# PHONE.net
KiCad netlist of a schematic drawn in Altium Designer
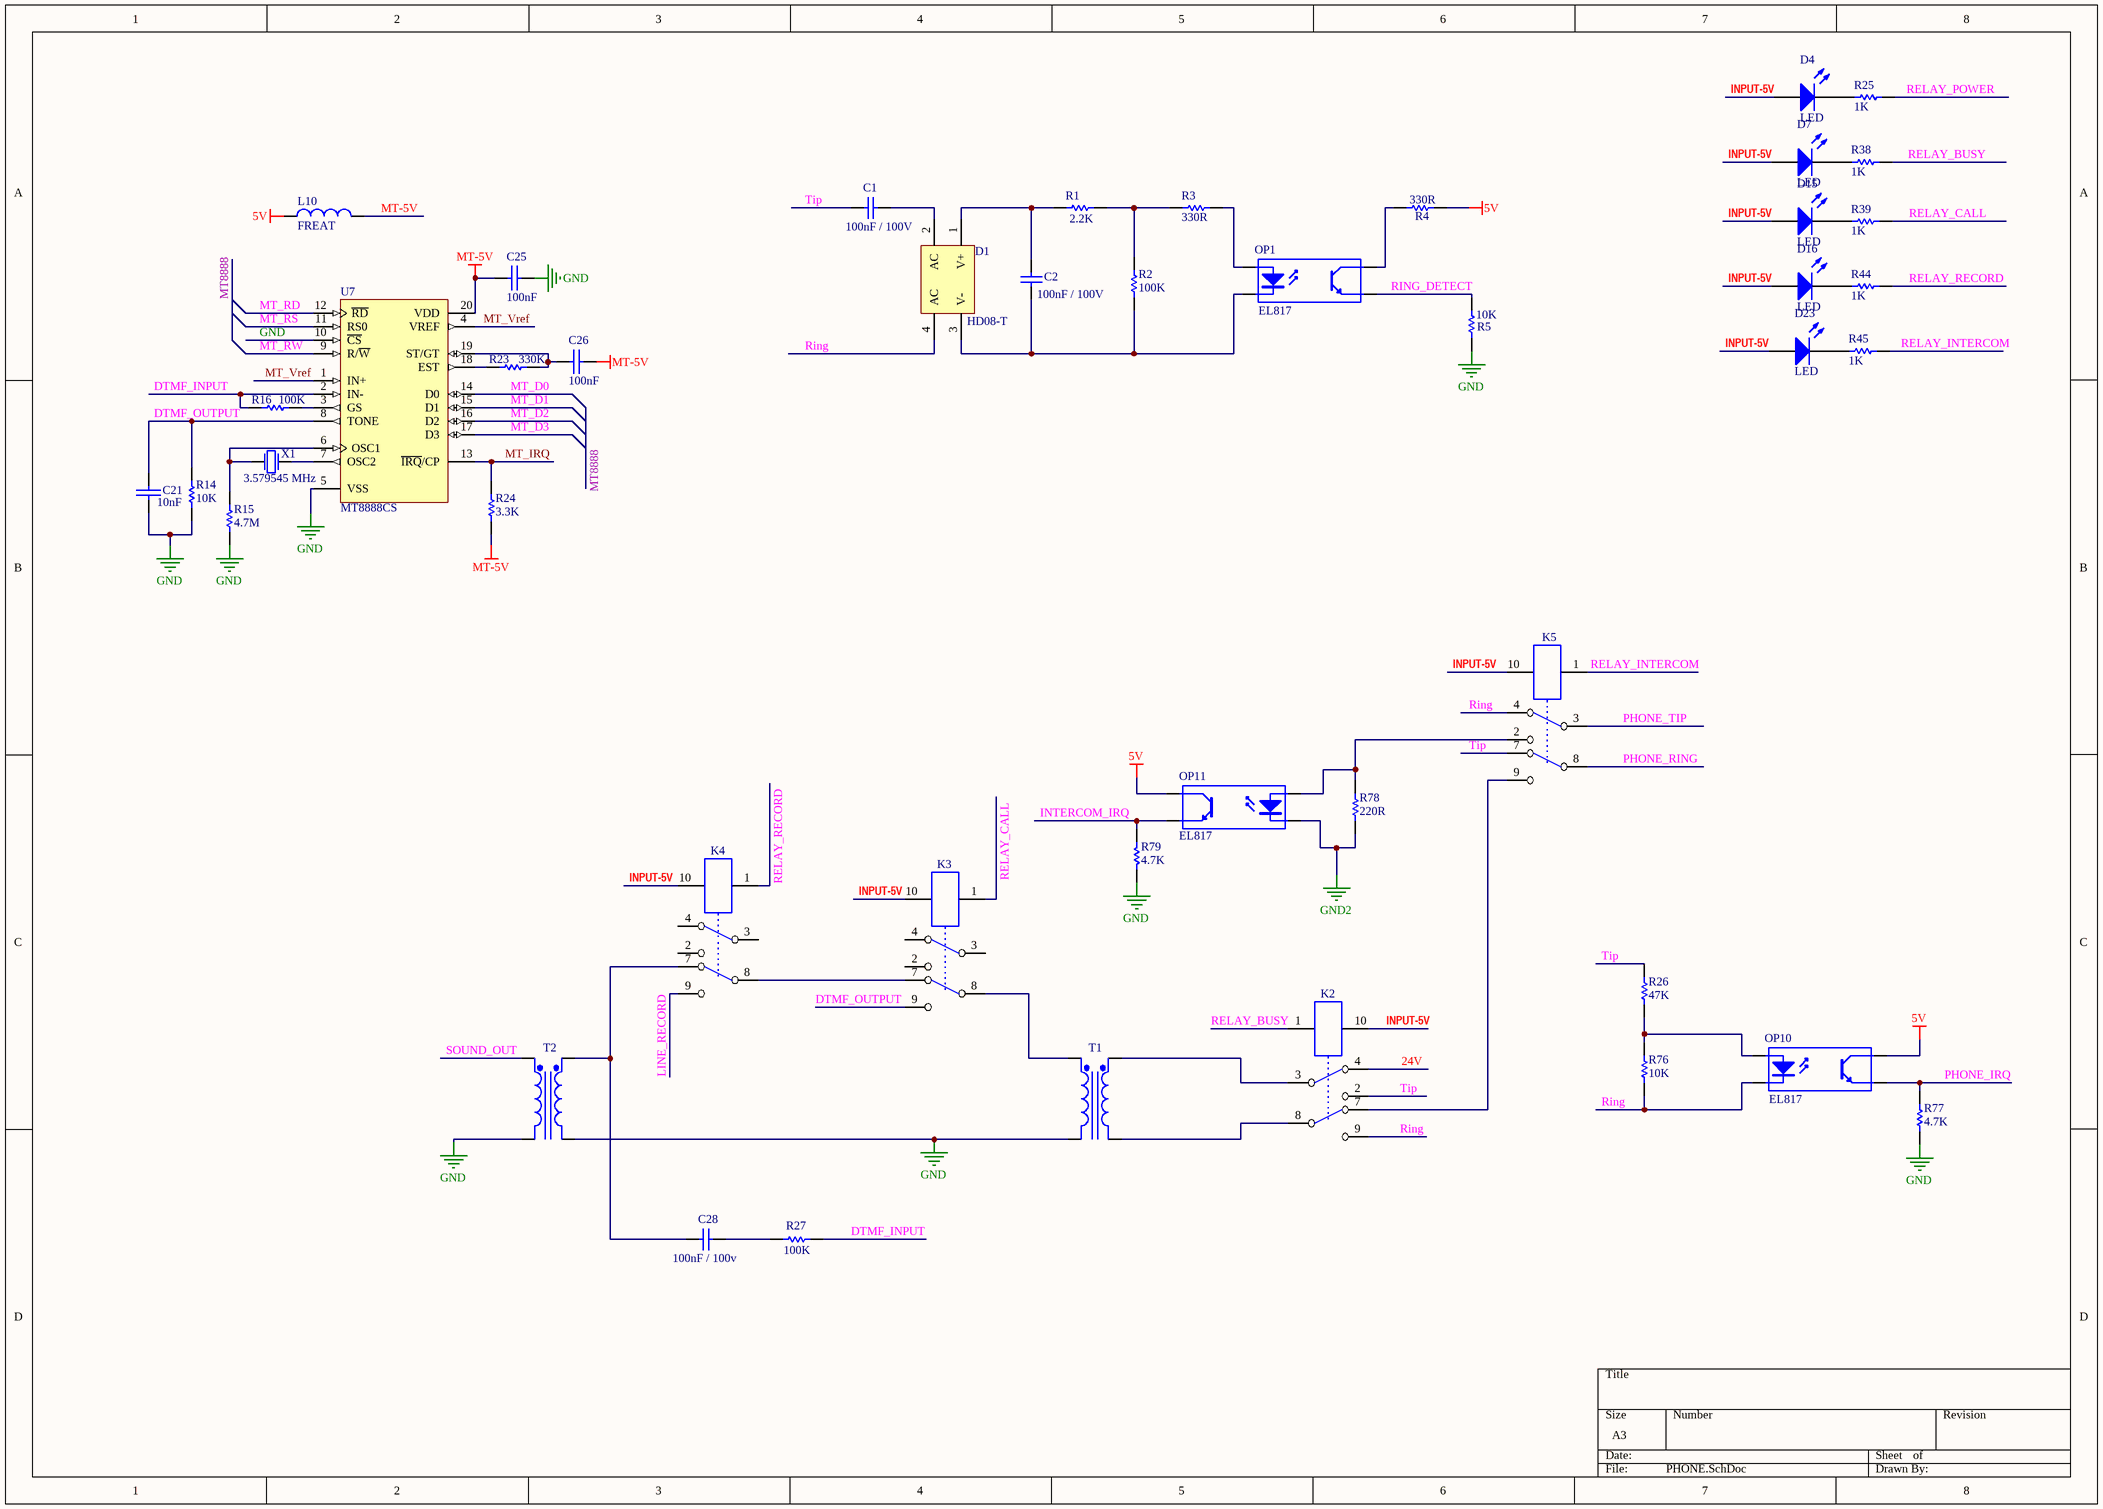
[diagram p0: PHONE.SchDoc]

(export (version "E")
  (design (tool "Eeschema 10.0.6"))
  (components
    (comp (ref "C1")
      (value "100nF / 100V")
      (footprint "RAD-0.3")
      (description "Capacitor")
      (fields (field (name "PUBLISHER") "Altium Limited"))
      (libsource (lib "Miscellaneous Devices") (part "Cap"))
    )
    (comp (ref "C2")
      (value "100nF / 100V")
      (footprint "RAD-0.3")
      (description "Capacitor")
      (fields (field (name "PUBLISHER") "Altium Limited"))
      (libsource (lib "Miscellaneous Devices") (part "Cap"))
    )
    (comp (ref "C21") (value "10nF") (footprint "0805c") (libsource (lib "*") (part "CAP")))
    (comp (ref "C25") (value "100nF") (footprint "0805c") (libsource (lib "*") (part "CAP")))
    (comp (ref "C26") (value "100nF") (footprint "0805c") (libsource (lib "*") (part "CAP")))
    (comp (ref "C28")
      (value "100nF / 100v")
      (footprint "1206")
      (description "Capacitor")
      (fields (field (name "Comment") "100uF / 100V") (field (name "PUBLISHER") "Altium Limited"))
      (libsource (lib "Miscellaneous Devices") (part "Cap"))
    )
    (comp (ref "D1")
      (value "HD08-T")
      (footprint "HD08-T")
      (description "Diode Bridge")
      (fields (field (name "PUBLISHER") "Altium Limited"))
      (libsource (lib "Miscellaneous Devices") (part "Bridge2"))
    )
    (comp (ref "D4")
      (value "LED")
      (footprint "0805d")
      (description "Typical RED GaAs LED")
      (fields (field (name "PUBLISHER") "Altium Limited"))
      (libsource (lib "Miscellaneous Devices") (part "LED1"))
    )
    (comp (ref "D7")
      (value "LED")
      (footprint "0805d")
      (description "Typical RED GaAs LED")
      (fields (field (name "PUBLISHER") "Altium Limited"))
      (libsource (lib "Miscellaneous Devices") (part "LED1"))
    )
    (comp (ref "D15")
      (value "LED")
      (footprint "0805d")
      (description "Typical RED GaAs LED")
      (fields (field (name "PUBLISHER") "Altium Limited"))
      (libsource (lib "Miscellaneous Devices") (part "LED1"))
    )
    (comp (ref "D16")
      (value "LED")
      (footprint "0805d")
      (description "Typical RED GaAs LED")
      (fields (field (name "PUBLISHER") "Altium Limited"))
      (libsource (lib "Miscellaneous Devices") (part "LED1"))
    )
    (comp (ref "D23")
      (value "LED")
      (footprint "0805d")
      (description "Typical RED GaAs LED")
      (fields (field (name "PUBLISHER") "Altium Limited"))
      (libsource (lib "Miscellaneous Devices") (part "LED1"))
    )
    (comp (ref "K2")
      (value "RELAY 5V")
      (footprint "RELAY G6H")
      (libsource (lib "*") (part "RELAY DPDT-G6HU"))
    )
    (comp (ref "K3")
      (value "RELAY 5V")
      (footprint "RELAY G6H")
      (libsource (lib "*") (part "RELAY DPDT-G6HU"))
    )
    (comp (ref "K4")
      (value "RELAY 5V")
      (footprint "RELAY G6H")
      (libsource (lib "*") (part "RELAY DPDT-G6HU"))
    )
    (comp (ref "K5")
      (value "RELAY 5V")
      (footprint "RELAY G6H")
      (libsource (lib "*") (part "RELAY DPDT-G6HU"))
    )
    (comp (ref "L10")
      (value "FREAT")
      (footprint "1206")
      (description "Inductor")
      (fields (field (name "PUBLISHER") "Altium Limited"))
      (libsource (lib "Miscellaneous Devices") (part "Inductor"))
    )
    (comp (ref "OP1")
      (value "EL817")
      (footprint "EL817")
      (description "4-Pin Phototransistor Optocoupler")
      (fields (field (name "PUBLISHER") "Altium Limited"))
      (libsource (lib "Miscellaneous Devices") (part "Optoisolator1"))
    )
    (comp (ref "OP10")
      (value "EL817")
      (footprint "EL817")
      (description "4-Pin Phototransistor Optocoupler")
      (fields (field (name "PUBLISHER") "Altium Limited"))
      (libsource (lib "Miscellaneous Devices") (part "Optoisolator1"))
    )
    (comp (ref "OP11")
      (value "EL817")
      (footprint "EL817")
      (description "4-Pin Phototransistor Optocoupler")
      (fields (field (name "PUBLISHER") "Altium Limited"))
      (libsource (lib "Miscellaneous Devices") (part "Optoisolator1"))
    )
    (comp (ref "R1")
      (value "2.2K")
      (footprint "0805")
      (description "Semiconductor Resistor")
      (fields (field (name "PUBLISHER") "Altium Limited"))
      (libsource (lib "Miscellaneous Devices") (part "Res Semi"))
    )
    (comp (ref "R2")
      (value "100K")
      (footprint "0805")
      (description "Semiconductor Resistor")
      (fields (field (name "PUBLISHER") "Altium Limited"))
      (libsource (lib "Miscellaneous Devices") (part "Res Semi"))
    )
    (comp (ref "R3")
      (value "330R")
      (footprint "0805")
      (description "Semiconductor Resistor")
      (fields (field (name "PUBLISHER") "Altium Limited"))
      (libsource (lib "Miscellaneous Devices") (part "Res Semi"))
    )
    (comp (ref "R4")
      (value "330R")
      (footprint "0805")
      (description "Semiconductor Resistor")
      (fields (field (name "PUBLISHER") "Altium Limited"))
      (libsource (lib "Miscellaneous Devices") (part "Res Semi"))
    )
    (comp (ref "R5")
      (value "10K")
      (footprint "0805")
      (description "Semiconductor Resistor")
      (fields (field (name "PUBLISHER") "Altium Limited"))
      (libsource (lib "Miscellaneous Devices") (part "Res Semi"))
    )
    (comp (ref "R14")
      (value "10K")
      (footprint "0805")
      (description "Semiconductor Resistor")
      (fields (field (name "PUBLISHER") "Altium Limited"))
      (libsource (lib "Miscellaneous Devices") (part "Res Semi"))
    )
    (comp (ref "R15")
      (value "4.7M")
      (footprint "0805")
      (description "Semiconductor Resistor")
      (fields (field (name "PUBLISHER") "Altium Limited"))
      (libsource (lib "Miscellaneous Devices") (part "Res Semi"))
    )
    (comp (ref "R16")
      (value "100K")
      (footprint "0805")
      (description "Semiconductor Resistor")
      (fields (field (name "PUBLISHER") "Altium Limited"))
      (libsource (lib "Miscellaneous Devices") (part "Res Semi"))
    )
    (comp (ref "R23")
      (value "330K")
      (footprint "0805")
      (description "Semiconductor Resistor")
      (fields (field (name "Comment") "374K") (field (name "PUBLISHER") "Altium Limited"))
      (libsource (lib "Miscellaneous Devices") (part "Res Semi"))
    )
    (comp (ref "R24")
      (value "3.3K")
      (footprint "0805")
      (description "Semiconductor Resistor")
      (fields (field (name "PUBLISHER") "Altium Limited"))
      (libsource (lib "Miscellaneous Devices") (part "Res Semi"))
    )
    (comp (ref "R25")
      (value "1K")
      (footprint "0805")
      (description "Resistor")
      (fields (field (name "PUBLISHER") "Altium Limited"))
      (libsource (lib "Miscellaneous Devices") (part "Res1"))
    )
    (comp (ref "R26")
      (value "47K")
      (footprint "0805")
      (description "Semiconductor Resistor")
      (fields (field (name "PUBLISHER") "Altium Limited"))
      (libsource (lib "Miscellaneous Devices") (part "Res Semi"))
    )
    (comp (ref "R27")
      (value "100K")
      (footprint "0805")
      (description "Semiconductor Resistor")
      (fields (field (name "PUBLISHER") "Altium Limited"))
      (libsource (lib "Miscellaneous Devices") (part "Res Semi"))
    )
    (comp (ref "R38")
      (value "1K")
      (footprint "0805")
      (description "Resistor")
      (fields (field (name "PUBLISHER") "Altium Limited"))
      (libsource (lib "Miscellaneous Devices") (part "Res1"))
    )
    (comp (ref "R39")
      (value "1K")
      (footprint "0805")
      (description "Resistor")
      (fields (field (name "PUBLISHER") "Altium Limited"))
      (libsource (lib "Miscellaneous Devices") (part "Res1"))
    )
    (comp (ref "R44")
      (value "1K")
      (footprint "0805")
      (description "Resistor")
      (fields (field (name "PUBLISHER") "Altium Limited"))
      (libsource (lib "Miscellaneous Devices") (part "Res1"))
    )
    (comp (ref "R45")
      (value "1K")
      (footprint "0805")
      (description "Resistor")
      (fields (field (name "PUBLISHER") "Altium Limited"))
      (libsource (lib "Miscellaneous Devices") (part "Res1"))
    )
    (comp (ref "R76")
      (value "10K")
      (footprint "0805")
      (description "Semiconductor Resistor")
      (fields (field (name "PUBLISHER") "Altium Limited"))
      (libsource (lib "Miscellaneous Devices") (part "Res Semi"))
    )
    (comp (ref "R77")
      (value "4.7K")
      (footprint "0805")
      (description "Semiconductor Resistor")
      (fields (field (name "PUBLISHER") "Altium Limited"))
      (libsource (lib "Miscellaneous Devices") (part "Res Semi"))
    )
    (comp (ref "R78")
      (value "220R")
      (footprint "0805")
      (description "Semiconductor Resistor")
      (fields (field (name "Comment") "220") (field (name "PUBLISHER") "Altium Limited"))
      (libsource (lib "Miscellaneous Devices") (part "Res Semi"))
    )
    (comp (ref "R79")
      (value "4.7K")
      (footprint "0805")
      (description "Semiconductor Resistor")
      (fields (field (name "PUBLISHER") "Altium Limited"))
      (libsource (lib "Miscellaneous Devices") (part "Res Semi"))
    )
    (comp (ref "T1")
      (value "TRANCE 300 :300")
      (footprint "trance")
      (description "Transformer (Ideal)")
      (fields (field (name "PUBLISHER") "Altium Limited"))
      (libsource (lib "Miscellaneous Devices") (part "Trans Ideal"))
    )
    (comp (ref "T2")
      (value "TRANCE 300 :300")
      (footprint "trance")
      (description "Transformer (Ideal)")
      (fields (field (name "PUBLISHER") "Altium Limited"))
      (libsource (lib "Miscellaneous Devices") (part "Trans Ideal"))
    )
    (comp (ref "U7")
      (value "MT8888CS")
      (footprint "SOIC20_N")
      (description "Integrated DTMF Transceiver with Intel Micro Interface")
      (fields (field (name "PUBLISHER") "Altium Limited"))
      (libsource (lib "Zarlink Comm DTMF Receiver") (part "MT8888CS"))
    )
    (comp (ref "X1")
      (value "3.579545 MHz")
      (footprint "crystal")
      (description "Crystal Oscillator")
      (libsource (lib "*") (part "16.000MHZ"))
    )
  )
  (nets
    (net (code "2") (name "/24V") (class "Default")
      (node (ref "K2") (pin "4") (pinfunction "NC1_4") (pintype "passive"))
    )
    (net (code "3") (name "/DTMF_INPUT") (class "Default")
      (node (ref "R16") (pin "2") (pinfunction "2_2") (pintype "passive"))
      (node (ref "R27") (pin "1") (pinfunction "1_1") (pintype "passive"))
      (node (ref "U7") (pin "2") (pinfunction "IN-_2") (pintype "input"))
    )
    (net (code "4") (name "/DTMF_OUTPUT") (class "Default")
      (node (ref "C21") (pin "1") (pintype "passive"))
      (node (ref "K3") (pin "9") (pinfunction "NO2_9") (pintype "passive"))
      (node (ref "R14") (pin "2") (pinfunction "2_2") (pintype "passive"))
      (node (ref "U7") (pin "8") (pinfunction "TONE_8") (pintype "output"))
    )
    (net (code "5") (name "/INPUT-5V") (class "Default")
      (node (ref "D15") (pin "1") (pinfunction "A_1") (pintype "passive"))
      (node (ref "D16") (pin "1") (pinfunction "A_1") (pintype "passive"))
      (node (ref "D23") (pin "1") (pinfunction "A_1") (pintype "passive"))
      (node (ref "D4") (pin "1") (pinfunction "A_1") (pintype "passive"))
      (node (ref "D7") (pin "1") (pinfunction "A_1") (pintype "passive"))
      (node (ref "K2") (pin "10") (pinfunction "-_10") (pintype "passive"))
      (node (ref "K3") (pin "10") (pinfunction "-_10") (pintype "passive"))
      (node (ref "K4") (pin "10") (pinfunction "-_10") (pintype "passive"))
      (node (ref "K5") (pin "10") (pinfunction "-_10") (pintype "passive"))
    )
    (net (code "6") (name "/INTERCOM_IRQ") (class "Default")
      (node (ref "OP11") (pin "3") (pinfunction "E_3") (pintype "passive"))
      (node (ref "R79") (pin "1") (pinfunction "1_1") (pintype "passive"))
    )
    (net (code "7") (name "/LINE_RECORD") (class "Default")
      (node (ref "K4") (pin "9") (pinfunction "NO2_9") (pintype "passive"))
    )
    (net (code "8") (name "/MT_D0") (class "Default")
      (node (ref "U7") (pin "14") (pinfunction "D0_14") (pintype "bidirectional"))
    )
    (net (code "9") (name "/MT_D1") (class "Default")
      (node (ref "U7") (pin "15") (pinfunction "D1_15") (pintype "bidirectional"))
    )
    (net (code "10") (name "/MT_D2") (class "Default")
      (node (ref "U7") (pin "16") (pinfunction "D2_16") (pintype "bidirectional"))
    )
    (net (code "11") (name "/MT_D3") (class "Default")
      (node (ref "U7") (pin "17") (pinfunction "D3_17") (pintype "bidirectional"))
    )
    (net (code "12") (name "/MT_IRQ") (class "Default")
      (node (ref "R24") (pin "2") (pinfunction "2_2") (pintype "passive"))
      (node (ref "U7") (pin "13") (pinfunction "~{IRQ}/CP_13") (pintype "open_collector"))
    )
    (net (code "13") (name "/MT_RD") (class "Default")
      (node (ref "U7") (pin "12") (pinfunction "~{RD}_12") (pintype "input"))
    )
    (net (code "14") (name "/MT_RS") (class "Default")
      (node (ref "U7") (pin "11") (pinfunction "RS0_11") (pintype "input"))
    )
    (net (code "15") (name "/MT_RW") (class "Default")
      (node (ref "U7") (pin "9") (pinfunction "R/~{W}_9") (pintype "input"))
    )
    (net (code "16") (name "/MT_Vref") (class "Default")
      (node (ref "U7") (pin "1") (pinfunction "IN+_1") (pintype "input"))
      (node (ref "U7") (pin "4") (pinfunction "VREF_4") (pintype "output"))
    )
    (net (code "17") (name "/PHONE_IRQ") (class "Default")
      (node (ref "OP10") (pin "3") (pinfunction "E_3") (pintype "passive"))
      (node (ref "R77") (pin "1") (pinfunction "1_1") (pintype "passive"))
    )
    (net (code "18") (name "/PHONE_RING") (class "Default")
      (node (ref "K5") (pin "8") (pinfunction "C2_8") (pintype "passive"))
    )
    (net (code "19") (name "/PHONE_TIP") (class "Default")
      (node (ref "K5") (pin "3") (pinfunction "C1_3") (pintype "passive"))
    )
    (net (code "20") (name "/RELAY_BUSY") (class "Default")
      (node (ref "K2") (pin "1") (pinfunction "+_1") (pintype "passive"))
      (node (ref "R38") (pin "2") (pinfunction "2_2") (pintype "passive"))
    )
    (net (code "21") (name "/RELAY_CALL") (class "Default")
      (node (ref "K3") (pin "1") (pinfunction "+_1") (pintype "passive"))
      (node (ref "R39") (pin "2") (pinfunction "2_2") (pintype "passive"))
    )
    (net (code "22") (name "/RELAY_INTERCOM") (class "Default")
      (node (ref "K5") (pin "1") (pinfunction "+_1") (pintype "passive"))
      (node (ref "R45") (pin "2") (pinfunction "2_2") (pintype "passive"))
    )
    (net (code "23") (name "/RELAY_POWER") (class "Default")
      (node (ref "R25") (pin "2") (pinfunction "2_2") (pintype "passive"))
    )
    (net (code "24") (name "/RELAY_RECORD") (class "Default")
      (node (ref "K4") (pin "1") (pinfunction "+_1") (pintype "passive"))
      (node (ref "R44") (pin "2") (pinfunction "2_2") (pintype "passive"))
    )
    (net (code "25") (name "/RING_DETECT") (class "Default")
      (node (ref "OP1") (pin "3") (pinfunction "E_3") (pintype "passive"))
      (node (ref "R5") (pin "2") (pinfunction "2_2") (pintype "passive"))
    )
    (net (code "26") (name "/Ring") (class "Default")
      (node (ref "D1") (pin "4") (pinfunction "AC_4") (pintype "passive"))
      (node (ref "K2") (pin "9") (pinfunction "NO2_9") (pintype "passive"))
      (node (ref "K5") (pin "4") (pinfunction "NC1_4") (pintype "passive"))
      (node (ref "OP10") (pin "2") (pinfunction "K_2") (pintype "passive"))
      (node (ref "R76") (pin "2") (pinfunction "2_2") (pintype "passive"))
    )
    (net (code "27") (name "/SOUND_OUT") (class "Default")
      (node (ref "T2") (pin "1") (pinfunction "Pri+_1") (pintype "passive"))
    )
    (net (code "28") (name "/Tip") (class "Default")
      (node (ref "C1") (pin "2") (pinfunction "2_2") (pintype "passive"))
      (node (ref "K2") (pin "2") (pinfunction "NO1_2") (pintype "passive"))
      (node (ref "K5") (pin "7") (pinfunction "NC2_7") (pintype "passive"))
      (node (ref "R26") (pin "2") (pinfunction "2_2") (pintype "passive"))
    )
    (net (code "30") (name "5V") (class "Default")
      (node (ref "L10") (pin "2") (pinfunction "2_2") (pintype "passive"))
      (node (ref "OP10") (pin "4") (pinfunction "C_4") (pintype "passive"))
      (node (ref "OP11") (pin "4") (pinfunction "C_4") (pintype "passive"))
      (node (ref "R4") (pin "2") (pinfunction "2_2") (pintype "passive"))
    )
    (net (code "31") (name "GND") (class "Default")
      (node (ref "C21") (pin "2") (pintype "passive"))
      (node (ref "C25") (pin "1") (pintype "passive"))
      (node (ref "R14") (pin "1") (pinfunction "1_1") (pintype "passive"))
      (node (ref "R15") (pin "1") (pinfunction "1_1") (pintype "passive"))
      (node (ref "R5") (pin "1") (pinfunction "1_1") (pintype "passive"))
      (node (ref "R77") (pin "2") (pinfunction "2_2") (pintype "passive"))
      (node (ref "R79") (pin "2") (pinfunction "2_2") (pintype "passive"))
      (node (ref "T1") (pin "2") (pinfunction "Pri-_2") (pintype "passive"))
      (node (ref "T2") (pin "2") (pinfunction "Pri-_2") (pintype "passive"))
      (node (ref "T2") (pin "4") (pinfunction "Sec-_4") (pintype "passive"))
      (node (ref "U7") (pin "10") (pinfunction "~{CS}_10") (pintype "input"))
      (node (ref "U7") (pin "5") (pinfunction "VSS_5") (pintype "power_in"))
    )
    (net (code "32") (name "GND2") (class "Default")
      (node (ref "OP11") (pin "2") (pinfunction "K_2") (pintype "passive"))
      (node (ref "R78") (pin "2") (pinfunction "2_2") (pintype "passive"))
    )
    (net (code "33") (name "MT-5V") (class "Default")
      (node (ref "C25") (pin "2") (pintype "passive"))
      (node (ref "C26") (pin "1") (pintype "passive"))
      (node (ref "L10") (pin "1") (pinfunction "1_1") (pintype "passive"))
      (node (ref "R24") (pin "1") (pinfunction "1_1") (pintype "passive"))
      (node (ref "U7") (pin "20") (pinfunction "VDD_20") (pintype "power_in"))
    )
    (net (code "34") (name "Net-(C1-Pad1)") (class "Default")
      (node (ref "C1") (pin "1") (pinfunction "1_1") (pintype "passive"))
      (node (ref "D1") (pin "2") (pinfunction "AC_2") (pintype "passive"))
    )
    (net (code "35") (name "Net-(C28-Pad2)") (class "Default")
      (node (ref "C28") (pin "2") (pinfunction "2_2") (pintype "passive"))
      (node (ref "R27") (pin "2") (pinfunction "2_2") (pintype "passive"))
    )
    (net (code "36") (name "Net-(D1-V+)") (class "Default")
      (node (ref "C2") (pin "2") (pinfunction "2_2") (pintype "passive"))
      (node (ref "D1") (pin "1") (pinfunction "V+_1") (pintype "passive"))
      (node (ref "R1") (pin "1") (pinfunction "1_1") (pintype "passive"))
    )
    (net (code "37") (name "Net-(D1-V-)") (class "Default")
      (node (ref "C2") (pin "1") (pinfunction "1_1") (pintype "passive"))
      (node (ref "D1") (pin "3") (pinfunction "V-_3") (pintype "passive"))
      (node (ref "OP1") (pin "2") (pinfunction "K_2") (pintype "passive"))
      (node (ref "R2") (pin "2") (pinfunction "2_2") (pintype "passive"))
    )
    (net (code "38") (name "Net-(D4-K)") (class "Default")
      (node (ref "D4") (pin "2") (pinfunction "K_2") (pintype "passive"))
      (node (ref "R25") (pin "1") (pinfunction "1_1") (pintype "passive"))
    )
    (net (code "39") (name "Net-(D7-K)") (class "Default")
      (node (ref "D7") (pin "2") (pinfunction "K_2") (pintype "passive"))
      (node (ref "R38") (pin "1") (pinfunction "1_1") (pintype "passive"))
    )
    (net (code "40") (name "Net-(D15-K)") (class "Default")
      (node (ref "D15") (pin "2") (pinfunction "K_2") (pintype "passive"))
      (node (ref "R39") (pin "1") (pinfunction "1_1") (pintype "passive"))
    )
    (net (code "41") (name "Net-(D16-K)") (class "Default")
      (node (ref "D16") (pin "2") (pinfunction "K_2") (pintype "passive"))
      (node (ref "R44") (pin "1") (pinfunction "1_1") (pintype "passive"))
    )
    (net (code "42") (name "Net-(D23-K)") (class "Default")
      (node (ref "D23") (pin "2") (pinfunction "K_2") (pintype "passive"))
      (node (ref "R45") (pin "1") (pinfunction "1_1") (pintype "passive"))
    )
    (net (code "43") (name "Net-(K2-C1)") (class "Default")
      (node (ref "K2") (pin "3") (pinfunction "C1_3") (pintype "passive"))
      (node (ref "T1") (pin "3") (pinfunction "Sec+_3") (pintype "passive"))
    )
    (net (code "44") (name "Net-(K2-C2)") (class "Default")
      (node (ref "K2") (pin "8") (pinfunction "C2_8") (pintype "passive"))
      (node (ref "T1") (pin "4") (pinfunction "Sec-_4") (pintype "passive"))
    )
    (net (code "45") (name "Net-(K2-NC2)") (class "Default")
      (node (ref "K2") (pin "7") (pinfunction "NC2_7") (pintype "passive"))
      (node (ref "K5") (pin "9") (pinfunction "NO2_9") (pintype "passive"))
    )
    (net (code "46") (name "Net-(K3-C2)") (class "Default")
      (node (ref "K3") (pin "8") (pinfunction "C2_8") (pintype "passive"))
      (node (ref "T1") (pin "1") (pinfunction "Pri+_1") (pintype "passive"))
    )
    (net (code "47") (name "Net-(K3-NC2)") (class "Default")
      (node (ref "K3") (pin "7") (pinfunction "NC2_7") (pintype "passive"))
      (node (ref "K4") (pin "8") (pinfunction "C2_8") (pintype "passive"))
    )
    (net (code "48") (name "Net-(K4-NC2)") (class "Default")
      (node (ref "C28") (pin "1") (pinfunction "1_1") (pintype "passive"))
      (node (ref "K4") (pin "7") (pinfunction "NC2_7") (pintype "passive"))
      (node (ref "T2") (pin "3") (pinfunction "Sec+_3") (pintype "passive"))
    )
    (net (code "49") (name "Net-(K5-NO1)") (class "Default")
      (node (ref "K5") (pin "2") (pinfunction "NO1_2") (pintype "passive"))
      (node (ref "OP11") (pin "1") (pinfunction "A_1") (pintype "passive"))
      (node (ref "R78") (pin "1") (pinfunction "1_1") (pintype "passive"))
    )
    (net (code "50") (name "Net-(OP1-A)") (class "Default")
      (node (ref "OP1") (pin "1") (pinfunction "A_1") (pintype "passive"))
      (node (ref "R3") (pin "2") (pinfunction "2_2") (pintype "passive"))
    )
    (net (code "51") (name "Net-(OP1-C)") (class "Default")
      (node (ref "OP1") (pin "4") (pinfunction "C_4") (pintype "passive"))
      (node (ref "R4") (pin "1") (pinfunction "1_1") (pintype "passive"))
    )
    (net (code "52") (name "Net-(OP10-A)") (class "Default")
      (node (ref "OP10") (pin "1") (pinfunction "A_1") (pintype "passive"))
      (node (ref "R26") (pin "1") (pinfunction "1_1") (pintype "passive"))
      (node (ref "R76") (pin "1") (pinfunction "1_1") (pintype "passive"))
    )
    (net (code "53") (name "Net-(R1-Pad2)") (class "Default")
      (node (ref "R1") (pin "2") (pinfunction "2_2") (pintype "passive"))
      (node (ref "R2") (pin "1") (pinfunction "1_1") (pintype "passive"))
      (node (ref "R3") (pin "1") (pinfunction "1_1") (pintype "passive"))
    )
    (net (code "54") (name "Net-(U7-EST)") (class "Default")
      (node (ref "R23") (pin "2") (pinfunction "2_2") (pintype "passive"))
      (node (ref "U7") (pin "18") (pinfunction "EST_18") (pintype "output"))
    )
    (net (code "55") (name "Net-(U7-GS)") (class "Default")
      (node (ref "R16") (pin "1") (pinfunction "1_1") (pintype "passive"))
      (node (ref "U7") (pin "3") (pinfunction "GS_3") (pintype "output"))
    )
    (net (code "56") (name "Net-(U7-OSC1)") (class "Default")
      (node (ref "R15") (pin "2") (pinfunction "2_2") (pintype "passive"))
      (node (ref "U7") (pin "6") (pinfunction "OSC1_6") (pintype "input"))
      (node (ref "X1") (pin "1") (pinfunction "P1_1") (pintype "passive"))
    )
    (net (code "57") (name "Net-(U7-OSC2)") (class "Default")
      (node (ref "U7") (pin "7") (pinfunction "OSC2_7") (pintype "output"))
      (node (ref "X1") (pin "2") (pinfunction "P2_2") (pintype "passive"))
    )
    (net (code "58") (name "Net-(U7-ST{slash}GT)") (class "Default")
      (node (ref "C26") (pin "2") (pintype "passive"))
      (node (ref "R23") (pin "1") (pinfunction "1_1") (pintype "passive"))
      (node (ref "U7") (pin "19") (pinfunction "ST/GT_19") (pintype "bidirectional"))
    )
    (net (code "59") (name "unconnected-(K3-C1-Pad3)") (class "Default")
      (node (ref "K3") (pin "3") (pinfunction "C1_3") (pintype "passive"))
    )
    (net (code "60") (name "unconnected-(K3-NC1-Pad4)") (class "Default")
      (node (ref "K3") (pin "4") (pinfunction "NC1_4") (pintype "passive"))
    )
    (net (code "61") (name "unconnected-(K3-NO1-Pad2)") (class "Default")
      (node (ref "K3") (pin "2") (pinfunction "NO1_2") (pintype "passive"))
    )
    (net (code "62") (name "unconnected-(K4-C1-Pad3)") (class "Default")
      (node (ref "K4") (pin "3") (pinfunction "C1_3") (pintype "passive"))
    )
    (net (code "63") (name "unconnected-(K4-NC1-Pad4)") (class "Default")
      (node (ref "K4") (pin "4") (pinfunction "NC1_4") (pintype "passive"))
    )
    (net (code "64") (name "unconnected-(K4-NO1-Pad2)") (class "Default")
      (node (ref "K4") (pin "2") (pinfunction "NO1_2") (pintype "passive"))
    )
  )
)
